# CSR8675_Minimun_System.net
KiCad netlist of a schematic drawn in EasyEDA Pro
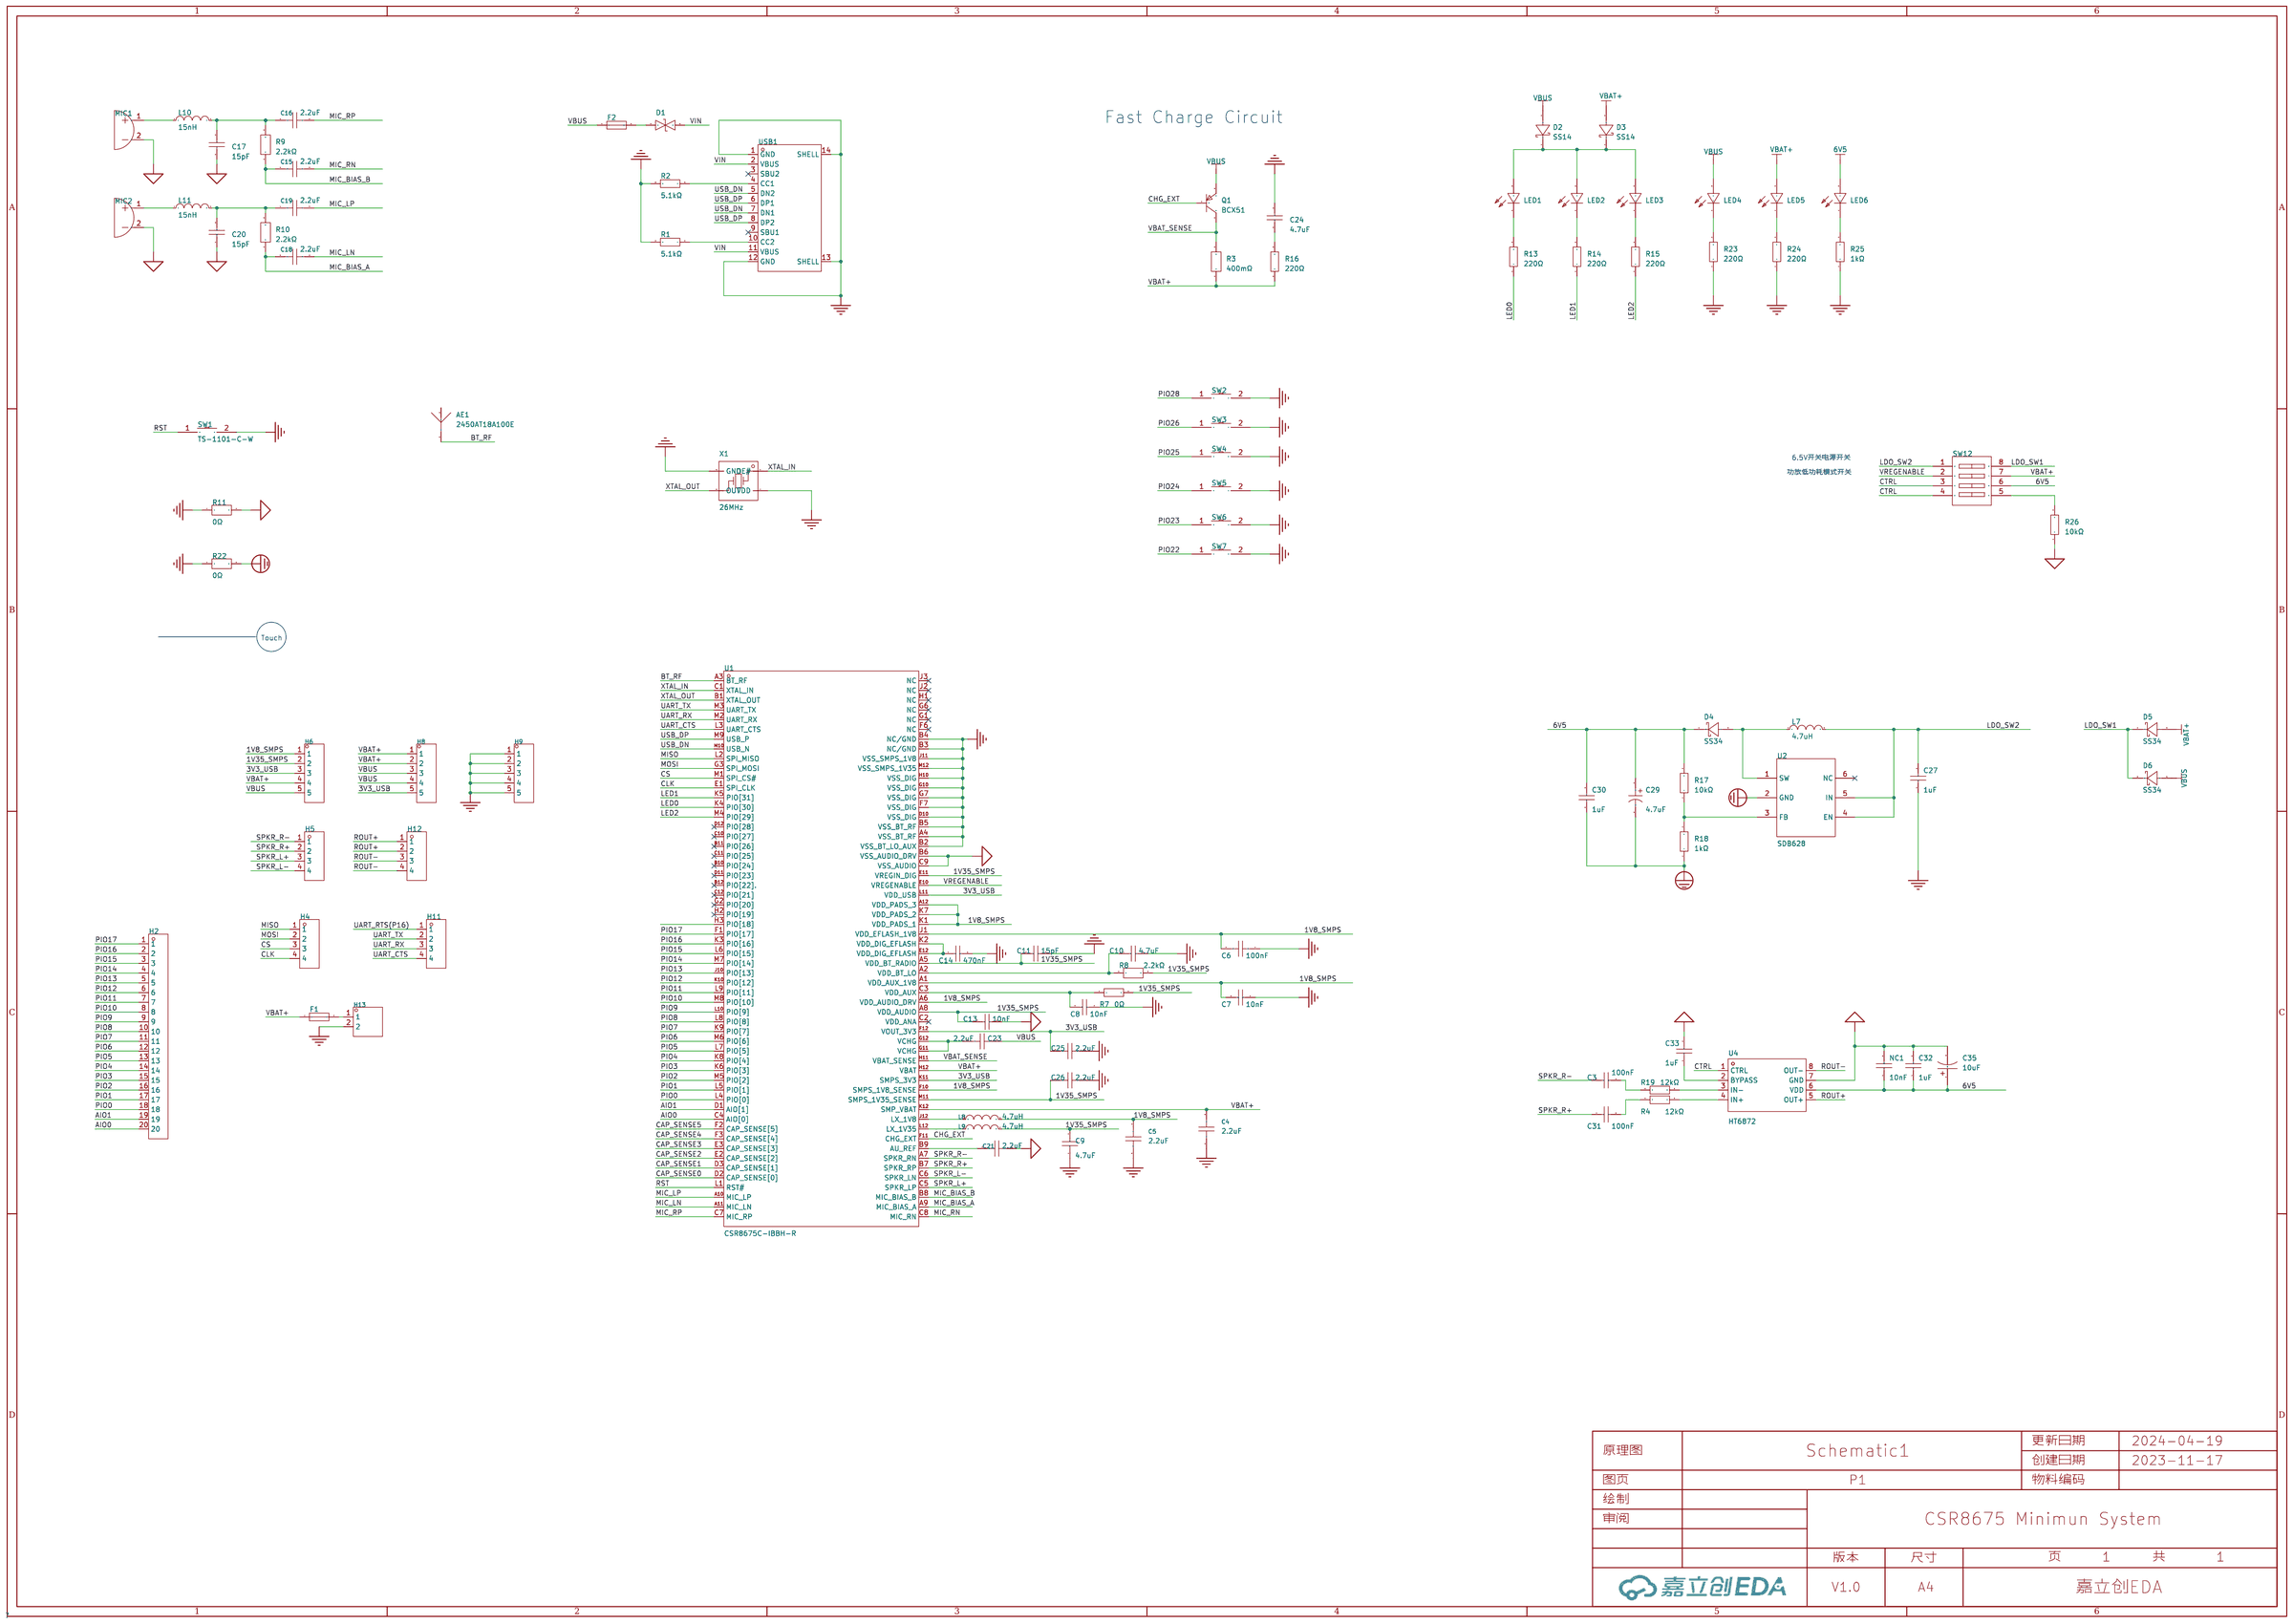
[diagram p0: schematic sheet]

(export (version "E")
  (design (tool "Eeschema 10.0.6"))
  (components
    (comp (ref "AE1")
      (value "2450AT18A100E")
      (footprint "easyedapro:ANT-SMD_L3.2-W1.6")
      (description "天线类型:2.4G天线;中心频点:2.4GHz;带宽:-;峰值增益:0.5dBi;极化方式:-;功率容量:2W;驻波比:-;")
      (fields (field (name "Manufacturer") "JOHANSON(约翰逊)"))
      (libsource (lib "easyedapro") (part "2450AT18A100E"))
    )
    (comp (ref "C3")
      (value "100nF")
      (footprint "easyedapro:C0603")
      (description "容值:100nF;精度:±10%;额定电压:50V;材质(温度系数):X7R;")
      (fields (field (name "Manufacturer Part") "0603B104K500NT") (field (name "Manufacturer") "FH(风华)"))
      (libsource (lib "easyedapro") (part "0603B104K500NT"))
    )
    (comp (ref "C4")
      (value "2.2uF")
      (footprint "easyedapro:C0603")
      (description "容值:2.2uF;精度:±10%;额定电压:50V;材质(温度系数):X5R;")
      (fields
        (field (name "Manufacturer Part") "CL10A225KB8NNNC")
        (field (name "Manufacturer") "SAMSUNG(三星)")
      )
      (libsource (lib "easyedapro") (part "CL10A225KB8NNNC"))
    )
    (comp (ref "C5")
      (value "2.2uF")
      (footprint "easyedapro:C0603")
      (description "容值:2.2uF;精度:±10%;额定电压:50V;材质(温度系数):X5R;")
      (fields
        (field (name "Manufacturer Part") "CL10A225KB8NNNC")
        (field (name "Manufacturer") "SAMSUNG(三星)")
      )
      (libsource (lib "easyedapro") (part "CL10A225KB8NNNC"))
    )
    (comp (ref "C6")
      (value "100nF")
      (footprint "easyedapro:C0603")
      (description "容值:100nF;精度:±10%;额定电压:50V;材质(温度系数):X7R;")
      (fields
        (field (name "Manufacturer Part") "CC0603KRX7R9BB104")
        (field (name "Manufacturer") "YAGEO(国巨)")
      )
      (libsource (lib "easyedapro") (part "CC0603KRX7R9BB104"))
    )
    (comp (ref "C7")
      (value "10nF")
      (footprint "easyedapro:C0603")
      (description "容值:10nF;精度:±10%;额定电压:50V;材质(温度系数):X7R;")
      (fields
        (field (name "Manufacturer Part") "CC0603KRX7R9BB103")
        (field (name "Manufacturer") "YAGEO(国巨)")
      )
      (libsource (lib "easyedapro") (part "CC0603KRX7R9BB103"))
    )
    (comp (ref "C8")
      (value "10nF")
      (footprint "easyedapro:C0603")
      (description "容值:10nF;精度:±10%;额定电压:50V;材质(温度系数):X7R;")
      (fields
        (field (name "Manufacturer Part") "CC0603KRX7R9BB103")
        (field (name "Manufacturer") "YAGEO(国巨)")
      )
      (libsource (lib "easyedapro") (part "CC0603KRX7R9BB103"))
    )
    (comp (ref "C9")
      (value "4.7uF")
      (footprint "easyedapro:C0805")
      (description "容值:4.7uF;精度:±10%;额定电压:25V;材质(温度系数):X5R;")
      (fields
        (field (name "Manufacturer Part") "CL21A475KAQNNNE")
        (field (name "Manufacturer") "SAMSUNG(三星)")
      )
      (libsource (lib "easyedapro") (part "CL21A475KAQNNNE"))
    )
    (comp (ref "C10")
      (value "4.7uF")
      (footprint "easyedapro:C0603")
      (description "容值:4.7uF;精度:±10%;额定电压:16V;材质(温度系数):X5R;")
      (fields
        (field (name "Manufacturer Part") "CL10A475KO8NNNC")
        (field (name "Manufacturer") "SAMSUNG(三星)")
      )
      (libsource (lib "easyedapro") (part "CL10A475KO8NNNC"))
    )
    (comp (ref "C11")
      (value "15pF")
      (footprint "easyedapro:C0603")
      (description "容值:15pF;精度:±5%;额定电压:50V;材质(温度系数):NP0;")
      (fields
        (field (name "Manufacturer Part") "CC0603JRNPO9BN150")
        (field (name "Manufacturer") "YAGEO(国巨)")
      )
      (libsource (lib "easyedapro") (part "CC0603JRNPO9BN150"))
    )
    (comp (ref "C13")
      (value "10nF")
      (footprint "easyedapro:C0603")
      (description "容值:10nF;精度:±10%;额定电压:50V;材质(温度系数):X7R;")
      (fields
        (field (name "Manufacturer Part") "CC0603KRX7R9BB103")
        (field (name "Manufacturer") "YAGEO(国巨)")
      )
      (libsource (lib "easyedapro") (part "CC0603KRX7R9BB103"))
    )
    (comp (ref "C14")
      (value "470nF")
      (footprint "easyedapro:C0603")
      (description "容值:470nF;精度:±10%;额定电压:25V;材质(温度系数):X7R;")
      (fields
        (field (name "Manufacturer Part") "CL10B474KA8NNNC")
        (field (name "Manufacturer") "SAMSUNG(三星)")
      )
      (libsource (lib "easyedapro") (part "CL10B474KA8NNNC"))
    )
    (comp (ref "C15")
      (value "2.2uF")
      (footprint "easyedapro:C0603")
      (description "容值:2.2uF;精度:±10%;额定电压:50V;材质(温度系数):X5R;")
      (fields
        (field (name "Manufacturer Part") "CL10A225KB8NNNC")
        (field (name "Manufacturer") "SAMSUNG(三星)")
      )
      (libsource (lib "easyedapro") (part "CL10A225KB8NNNC"))
    )
    (comp (ref "C16")
      (value "2.2uF")
      (footprint "easyedapro:C0603")
      (description "容值:2.2uF;精度:±10%;额定电压:50V;材质(温度系数):X5R;")
      (fields
        (field (name "Manufacturer Part") "CL10A225KB8NNNC")
        (field (name "Manufacturer") "SAMSUNG(三星)")
      )
      (libsource (lib "easyedapro") (part "CL10A225KB8NNNC"))
    )
    (comp (ref "C17")
      (value "15pF")
      (footprint "easyedapro:C0603")
      (description "容值:15pF;精度:±5%;额定电压:50V;材质(温度系数):NP0;")
      (fields
        (field (name "Manufacturer Part") "CC0603JRNPO9BN150")
        (field (name "Manufacturer") "YAGEO(国巨)")
      )
      (libsource (lib "easyedapro") (part "CC0603JRNPO9BN150"))
    )
    (comp (ref "C18")
      (value "2.2uF")
      (footprint "easyedapro:C0603")
      (description "容值:2.2uF;精度:±10%;额定电压:50V;材质(温度系数):X5R;")
      (fields
        (field (name "Manufacturer Part") "CL10A225KB8NNNC")
        (field (name "Manufacturer") "SAMSUNG(三星)")
      )
      (libsource (lib "easyedapro") (part "CL10A225KB8NNNC"))
    )
    (comp (ref "C19")
      (value "2.2uF")
      (footprint "easyedapro:C0603")
      (description "容值:2.2uF;精度:±10%;额定电压:50V;材质(温度系数):X5R;")
      (fields
        (field (name "Manufacturer Part") "CL10A225KB8NNNC")
        (field (name "Manufacturer") "SAMSUNG(三星)")
      )
      (libsource (lib "easyedapro") (part "CL10A225KB8NNNC"))
    )
    (comp (ref "C20")
      (value "15pF")
      (footprint "easyedapro:C0603")
      (description "容值:15pF;精度:±5%;额定电压:50V;材质(温度系数):NP0;")
      (fields
        (field (name "Manufacturer Part") "CC0603JRNPO9BN150")
        (field (name "Manufacturer") "YAGEO(国巨)")
      )
      (libsource (lib "easyedapro") (part "CC0603JRNPO9BN150"))
    )
    (comp (ref "C21")
      (value "2.2uF")
      (footprint "easyedapro:C0603")
      (description "容值:2.2uF;精度:±10%;额定电压:50V;材质(温度系数):X5R;")
      (fields
        (field (name "Manufacturer Part") "CL10A225KB8NNNC")
        (field (name "Manufacturer") "SAMSUNG(三星)")
      )
      (libsource (lib "easyedapro") (part "CL10A225KB8NNNC"))
    )
    (comp (ref "C23")
      (value "2.2uF")
      (footprint "easyedapro:C0805")
      (description "容值:2.2uF;精度:±10%;额定电压:100V;材质(温度系数):X7T;")
      (fields
        (field (name "Manufacturer Part") "GRM21BD72A225KE01L")
        (field (name "Manufacturer") "muRata(村田)")
      )
      (libsource (lib "easyedapro") (part "GRM21BD72A225KE01L"))
    )
    (comp (ref "C24")
      (value "4.7uF")
      (footprint "easyedapro:C0805")
      (description "容值:4.7uF;精度:±10%;额定电压:25V;材质(温度系数):X5R;")
      (fields
        (field (name "Manufacturer Part") "CL21A475KAQNNNE")
        (field (name "Manufacturer") "SAMSUNG(三星)")
      )
      (libsource (lib "easyedapro") (part "CL21A475KAQNNNE"))
    )
    (comp (ref "C25")
      (value "2.2uF")
      (footprint "easyedapro:C0805")
      (description "容值:2.2uF;精度:±10%;额定电压:100V;材质(温度系数):X7T;")
      (fields
        (field (name "Manufacturer Part") "GRM21BD72A225KE01L")
        (field (name "Manufacturer") "muRata(村田)")
      )
      (libsource (lib "easyedapro") (part "GRM21BD72A225KE01L"))
    )
    (comp (ref "C26")
      (value "2.2uF")
      (footprint "easyedapro:C0805")
      (description "容值:2.2uF;精度:±10%;额定电压:100V;材质(温度系数):X7T;")
      (fields
        (field (name "Manufacturer Part") "GRM21BD72A225KE01L")
        (field (name "Manufacturer") "muRata(村田)")
      )
      (libsource (lib "easyedapro") (part "GRM21BD72A225KE01L"))
    )
    (comp (ref "C27")
      (value "1uF")
      (footprint "easyedapro:C0603")
      (description "容值:1uF;精度:±10%;额定电压:50V;材质(温度系数):X5R;")
      (fields
        (field (name "Manufacturer Part") "CL10A105KB8NNNC")
        (field (name "Manufacturer") "SAMSUNG(三星)")
      )
      (libsource (lib "easyedapro") (part "CL10A105KB8NNNC"))
    )
    (comp (ref "C29")
      (value "4.7uF")
      (footprint "easyedapro:CAP-TH_BD5.0-P2.00-D0.5-FD")
      (description "容值:4.7uF;精度:±20%;额定电压:50V;纹波电流:-;等效串联电阻:-;")
      (fields (field (name "Manufacturer Part") "KM1H4R7M0407") (field (name "Manufacturer") "ROQANG(容强)"))
      (libsource (lib "easyedapro") (part "KM1H4R7M0407"))
    )
    (comp (ref "C30")
      (value "1uF")
      (footprint "easyedapro:C0603")
      (description "容值:1uF;精度:±10%;额定电压:50V;材质(温度系数):X5R;")
      (fields
        (field (name "Manufacturer Part") "CL10A105KB8NNNC")
        (field (name "Manufacturer") "SAMSUNG(三星)")
      )
      (libsource (lib "easyedapro") (part "CL10A105KB8NNNC"))
    )
    (comp (ref "C31")
      (value "100nF")
      (footprint "easyedapro:C0603")
      (description "容值:100nF;精度:±10%;额定电压:50V;材质(温度系数):X7R;")
      (fields (field (name "Manufacturer Part") "0603B104K500NT") (field (name "Manufacturer") "FH(风华)"))
      (libsource (lib "easyedapro") (part "0603B104K500NT"))
    )
    (comp (ref "C32")
      (value "1uF")
      (footprint "easyedapro:C0603")
      (description "容值:1uF;精度:±10%;额定电压:50V;材质(温度系数):X5R;")
      (fields
        (field (name "Manufacturer Part") "CL10A105KB8NNNC")
        (field (name "Manufacturer") "SAMSUNG(三星)")
      )
      (libsource (lib "easyedapro") (part "CL10A105KB8NNNC"))
    )
    (comp (ref "C33")
      (value "1uF")
      (footprint "easyedapro:C0603")
      (description "容值:1uF;精度:±10%;额定电压:50V;材质(温度系数):X5R;")
      (fields
        (field (name "Manufacturer Part") "CL10A105KB8NNNC")
        (field (name "Manufacturer") "SAMSUNG(三星)")
      )
      (libsource (lib "easyedapro") (part "CL10A105KB8NNNC"))
    )
    (comp (ref "C35")
      (value "10uF")
      (footprint "easyedapro:CAP-TH_BD5.0-P2.00-D0.8-FD")
      (description "容值:10uF;精度:±20%;额定电压:50V;纹波电流:50mA@120Hz;等效串联电阻:-;")
      (fields
        (field (name "Manufacturer Part") "01EC1809SHC10UF50V")
        (field (name "Manufacturer") "KNSCHA(科尼盛)")
      )
      (libsource (lib "easyedapro") (part "01EC1809SHC10UF50V"))
    )
    (comp (ref "D1")
      (value "0603ESDA-05N")
      (footprint "easyedapro:D0603-BI")
      (description "极性:双向;反向截止电压(Vrwm):5V;最大钳位电压:50V;")
      (fields (field (name "Manufacturer") "BORN(伯恩半导体)"))
      (libsource (lib "easyedapro") (part "0603ESDA-05N"))
    )
    (comp (ref "D2")
      (value "SS14")
      (footprint "easyedapro:SOD-123FL_L2.8-W1.8-LS3.7-RD")
      (description "二极管配置:-;正向压降(Vf):550mV@1A;直流反向耐压(Vr):40V;平均整流电流(Io):1A;")
      (fields (field (name "Manufacturer") "KUU"))
      (libsource (lib "easyedapro") (part "SS14_C2909920"))
    )
    (comp (ref "D3")
      (value "SS14")
      (footprint "easyedapro:SOD-123FL_L2.8-W1.8-LS3.7-RD")
      (description "二极管配置:-;正向压降(Vf):550mV@1A;直流反向耐压(Vr):40V;平均整流电流(Io):1A;")
      (fields (field (name "Manufacturer") "KUU"))
      (libsource (lib "easyedapro") (part "SS14_C2909920"))
    )
    (comp (ref "D4")
      (value "SS34")
      (footprint "easyedapro:SMA_L4.3-W2.5-LS5.0-RD")
      (description "二极管配置:独立式;正向压降(Vf):550mV@3A;直流反向耐压(Vr):40V;平均整流电流(Io):3A;")
      (fields (field (name "Manufacturer") "TWGMC(台湾迪嘉)"))
      (libsource (lib "easyedapro") (part "SS34_C727060"))
    )
    (comp (ref "D5")
      (value "SS34")
      (footprint "easyedapro:SMA_L4.3-W2.5-LS5.0-RD")
      (description "二极管配置:独立式;正向压降(Vf):550mV@3A;直流反向耐压(Vr):40V;平均整流电流(Io):3A;")
      (fields (field (name "Manufacturer") "TWGMC(台湾迪嘉)"))
      (libsource (lib "easyedapro") (part "SS34_C727060"))
    )
    (comp (ref "D6")
      (value "SS34")
      (footprint "easyedapro:SMA_L4.3-W2.5-LS5.0-RD")
      (description "二极管配置:独立式;正向压降(Vf):550mV@3A;直流反向耐压(Vr):40V;平均整流电流(Io):3A;")
      (fields (field (name "Manufacturer") "TWGMC(台湾迪嘉)"))
      (libsource (lib "easyedapro") (part "SS34_C727060"))
    )
    (comp (ref "F1")
      (value "BSMD1210L-500")
      (footprint "easyedapro:F1210")
      (description "最大电压:6V;最大电流:50A;保持电流:5A;跳闸电流:10A;")
      (fields (field (name "Manufacturer") "BHFUSE(佰宏)"))
      (libsource (lib "easyedapro") (part "BSMD1210L-500"))
    )
    (comp (ref "F2")
      (value "BSMD1210L-500")
      (footprint "easyedapro:F1210")
      (description "最大电压:6V;最大电流:50A;保持电流:5A;跳闸电流:10A;")
      (fields (field (name "Manufacturer") "BHFUSE(佰宏)"))
      (libsource (lib "easyedapro") (part "BSMD1210L-500"))
    )
    (comp (ref "H2")
      (value "~")
      (footprint "easyedapro:HDR-TH_20P-P2.54-V-M-1")
      (libsource (lib "easyedapro") (part "HDR_2.54-1x20P"))
    )
    (comp (ref "H4")
      (value "~")
      (footprint "easyedapro:HDR-TH_4P-P2.54-V-M")
      (libsource (lib "easyedapro") (part "PZ254V-11-04P"))
    )
    (comp (ref "H5")
      (value "~")
      (footprint "easyedapro:HDR-TH_4P-P2.54-V-M")
      (libsource (lib "easyedapro") (part "PZ254V-11-04P"))
    )
    (comp (ref "H6")
      (value "~")
      (footprint "easyedapro:HDR-TH_5P-P2.54-V-M")
      (libsource (lib "easyedapro") (part "MTP125-1105S1"))
    )
    (comp (ref "H8")
      (value "~")
      (footprint "easyedapro:HDR-TH_5P-P2.54-V-M")
      (libsource (lib "easyedapro") (part "MTP125-1105S1"))
    )
    (comp (ref "H9")
      (value "~")
      (footprint "easyedapro:HDR-TH_5P-P2.54-V-M")
      (libsource (lib "easyedapro") (part "MTP125-1105S1"))
    )
    (comp (ref "H11")
      (value "~")
      (footprint "easyedapro:HDR-TH_4P-P2.54-V-M")
      (libsource (lib "easyedapro") (part "PZ254V-11-04P"))
    )
    (comp (ref "H12")
      (value "~")
      (footprint "easyedapro:HDR-TH_4P-P2.54-V-M")
      (libsource (lib "easyedapro") (part "PZ254V-11-04P"))
    )
    (comp (ref "H13")
      (value "~")
      (footprint "easyedapro:HDR-TH_2P-P2.54-V-M-1")
      (libsource (lib "easyedapro") (part "210S-1*2P L=11.6MMGold-plated black"))
    )
    (comp (ref "L7")
      (value "4.7uH")
      (footprint "easyedapro:IND-SMD_L4.4-W4.2")
      (description "电感值:4.7uH;精度:±20%;额定电流:2.8A;饱和电流(Isat):3A;类型:一体成型电感;")
      (fields (field (name "Manufacturer Part") "FXL0420-4R7-M") (field (name "Manufacturer") "cjiang(长江微电)"))
      (libsource (lib "easyedapro") (part "FXL0420-4R7-M"))
    )
    (comp (ref "L8")
      (value "4.7uH")
      (footprint "easyedapro:L0805")
      (description "电感值:4.7uH;精度:±20%;额定电流:800mA;饱和电流(Isat):-;直流电阻(DCR):288mΩ;")
      (fields (field (name "Manufacturer Part") "LQM21PN4R7MGRD") (field (name "Manufacturer") "muRata(村田)"))
      (libsource (lib "easyedapro") (part "LQM21PN4R7MGRD"))
    )
    (comp (ref "L9")
      (value "4.7uH")
      (footprint "easyedapro:L0805")
      (description "电感值:4.7uH;精度:±20%;额定电流:800mA;饱和电流(Isat):-;直流电阻(DCR):288mΩ;")
      (fields (field (name "Manufacturer Part") "LQM21PN4R7MGRD") (field (name "Manufacturer") "muRata(村田)"))
      (libsource (lib "easyedapro") (part "LQM21PN4R7MGRD"))
    )
    (comp (ref "L10")
      (value "15nH")
      (footprint "easyedapro:L0805")
      (description "电感值:15nH;精度:±5%;额定电流:300mA;饱和电流(Isat):-;直流电阻(DCR):400mΩ;")
      (fields (field (name "Manufacturer Part") "VHF201209H15NJT") (field (name "Manufacturer") "FH(风华)"))
      (libsource (lib "easyedapro") (part "VHF201209H15NJT"))
    )
    (comp (ref "L11")
      (value "15nH")
      (footprint "easyedapro:L0805")
      (description "电感值:15nH;精度:±5%;额定电流:300mA;饱和电流(Isat):-;直流电阻(DCR):400mΩ;")
      (fields (field (name "Manufacturer Part") "VHF201209H15NJT") (field (name "Manufacturer") "FH(风华)"))
      (libsource (lib "easyedapro") (part "VHF201209H15NJT"))
    )
    (comp (ref "LED1")
      (value "NCD0603R1")
      (footprint "easyedapro:LED0603-RD_RED")
      (fields (field (name "Manufacturer") "国星光电"))
      (libsource (lib "easyedapro") (part "FC-DA1608HRK-620D"))
    )
    (comp (ref "LED2")
      (value "NCD0603R1")
      (footprint "easyedapro:LED0603-RD_RED")
      (fields (field (name "Manufacturer") "国星光电"))
      (libsource (lib "easyedapro") (part "FC-DA1608HRK-620D"))
    )
    (comp (ref "LED3")
      (value "NCD0603R1")
      (footprint "easyedapro:LED0603-RD_RED")
      (fields (field (name "Manufacturer") "国星光电"))
      (libsource (lib "easyedapro") (part "FC-DA1608HRK-620D"))
    )
    (comp (ref "LED4")
      (value "NCD0603R1")
      (footprint "easyedapro:LED0603-RD_RED")
      (fields (field (name "Manufacturer") "国星光电"))
      (libsource (lib "easyedapro") (part "FC-DA1608HRK-620D"))
    )
    (comp (ref "LED5")
      (value "NCD0603R1")
      (footprint "easyedapro:LED0603-RD_RED")
      (fields (field (name "Manufacturer") "国星光电"))
      (libsource (lib "easyedapro") (part "FC-DA1608HRK-620D"))
    )
    (comp (ref "LED6")
      (value "NCD0603R1")
      (footprint "easyedapro:LED0603-RD_RED")
      (fields (field (name "Manufacturer") "国星光电"))
      (libsource (lib "easyedapro") (part "FC-DA1608HRK-620D"))
    )
    (comp (ref "MIC1")
      (value "GMI6027P-34DB")
      (footprint "easyedapro:MIC-TH_BD6.0-P1.90-D0.4-L")
      (fields (field (name "Manufacturer") "INGHAi(赢海)"))
      (libsource (lib "easyedapro") (part "GMI6027P-34DB"))
    )
    (comp (ref "MIC2")
      (value "GMI6027P-34DB")
      (footprint "easyedapro:MIC-TH_BD6.0-P1.90-D0.4-L")
      (fields (field (name "Manufacturer") "INGHAi(赢海)"))
      (libsource (lib "easyedapro") (part "GMI6027P-34DB"))
    )
    (comp (ref "NC1")
      (value "10nF")
      (footprint "easyedapro:C0603")
      (description "容值:10nF;精度:±10%;额定电压:50V;材质(温度系数):X7R;")
      (fields
        (field (name "Manufacturer Part") "CC0603KRX7R9BB103")
        (field (name "Manufacturer") "YAGEO(国巨)")
      )
      (libsource (lib "easyedapro") (part "CC0603KRX7R9BB103"))
    )
    (comp (ref "Q1")
      (value "BCX51")
      (footprint "easyedapro:SOT-89-3_L4.5-W2.5-P1.50-LS4.2-BR")
      (description "晶体管类型:PNP;集电极电流(Ic):1A;集射极击穿电压(Vceo):45V;功率(Pd):1W;直流电流增益(hFE@Ic,Vce):25@5mA,2V;")
      (fields (field (name "Manufacturer") "SHIKUES(时科)"))
      (libsource (lib "easyedapro") (part "BCX51"))
    )
    (comp (ref "R1")
      (value "5.1kΩ")
      (footprint "easyedapro:R0603")
      (description "电阻类型:厚膜电阻;阻值:5.1kΩ;精度:±1%;功率:100mW;最大工作电压:75V;温度系数:±100ppm/°C;")
      (fields
        (field (name "Manufacturer Part") "0603WAF5101T5E")
        (field (name "Manufacturer") "UNI-ROYAL(厚声)")
      )
      (libsource (lib "easyedapro") (part "0603WAF5101T5E"))
    )
    (comp (ref "R2")
      (value "5.1kΩ")
      (footprint "easyedapro:R0603")
      (description "电阻类型:厚膜电阻;阻值:5.1kΩ;精度:±1%;功率:100mW;最大工作电压:75V;温度系数:±100ppm/°C;")
      (fields
        (field (name "Manufacturer Part") "0603WAF5101T5E")
        (field (name "Manufacturer") "UNI-ROYAL(厚声)")
      )
      (libsource (lib "easyedapro") (part "0603WAF5101T5E"))
    )
    (comp (ref "R3")
      (value "400mΩ")
      (footprint "easyedapro:R0805")
      (description "电阻类型:厚膜电阻;阻值:400mΩ;精度:±1%;功率:125mW;最大工作电压:300V;温度系数:±300ppm/°C;")
      (fields (field (name "Manufacturer Part") "FRL0805FR400TS") (field (name "Manufacturer") "FOJAN(富捷)"))
      (libsource (lib "easyedapro") (part "FRL0805FR400TS"))
    )
    (comp (ref "R4")
      (value "12kΩ")
      (footprint "easyedapro:R0603")
      (description "电阻类型:厚膜电阻;阻值:12kΩ;精度:±1%;功率:100mW;最大工作电压:75V;温度系数:±100ppm/°C;")
      (fields
        (field (name "Manufacturer Part") "0603WAF1202T5E")
        (field (name "Manufacturer") "UNI-ROYAL(厚声)")
      )
      (libsource (lib "easyedapro") (part "0603WAF1202T5E"))
    )
    (comp (ref "R7")
      (value "0Ω")
      (footprint "easyedapro:R0603")
      (description "电阻类型:厚膜电阻;阻值:0Ω;精度:±1%;功率:100mW;最大工作电压:75V;")
      (fields
        (field (name "Manufacturer Part") "0603WAF0000T5E")
        (field (name "Manufacturer") "UNI-ROYAL(厚声)")
      )
      (libsource (lib "easyedapro") (part "0603WAF0000T5E"))
    )
    (comp (ref "R8")
      (value "2.2kΩ")
      (footprint "easyedapro:R0603")
      (description "电阻类型:厚膜电阻;阻值:2.2kΩ;精度:±5%;功率:100mW;最大工作电压:75V;温度系数:±100ppm/°C;")
      (fields (field (name "Manufacturer Part") "FRC0603J222 TS") (field (name "Manufacturer") "FOJAN(富捷)"))
      (libsource (lib "easyedapro") (part "FRC0603J222 TS"))
    )
    (comp (ref "R9")
      (value "2.2kΩ")
      (footprint "easyedapro:R0603")
      (description "电阻类型:厚膜电阻;阻值:2.2kΩ;精度:±5%;功率:100mW;最大工作电压:75V;温度系数:±100ppm/°C;")
      (fields (field (name "Manufacturer Part") "FRC0603J222 TS") (field (name "Manufacturer") "FOJAN(富捷)"))
      (libsource (lib "easyedapro") (part "FRC0603J222 TS"))
    )
    (comp (ref "R10")
      (value "2.2kΩ")
      (footprint "easyedapro:R0603")
      (description "电阻类型:厚膜电阻;阻值:2.2kΩ;精度:±5%;功率:100mW;最大工作电压:75V;温度系数:±100ppm/°C;")
      (fields (field (name "Manufacturer Part") "FRC0603J222 TS") (field (name "Manufacturer") "FOJAN(富捷)"))
      (libsource (lib "easyedapro") (part "FRC0603J222 TS"))
    )
    (comp (ref "R11")
      (value "0Ω")
      (footprint "easyedapro:R0805")
      (description "电阻类型:厚膜电阻;阻值:0Ω;精度:±5%;功率:125mW;最大工作电压:150V;")
      (fields (field (name "Manufacturer Part") "FRC0805P000 TS") (field (name "Manufacturer") "FOJAN(富捷)"))
      (libsource (lib "easyedapro") (part "FRC0805P000 TS"))
    )
    (comp (ref "R13")
      (value "220Ω")
      (footprint "easyedapro:R0603")
      (description "电阻类型:厚膜电阻;阻值:220Ω;精度:±5%;功率:100mW;最大工作电压:75V;温度系数:±100ppm/°C;")
      (fields
        (field (name "Manufacturer Part") "0603WAJ0221T5E")
        (field (name "Manufacturer") "UNI-ROYAL(厚声)")
      )
      (libsource (lib "easyedapro") (part "0603WAJ0221T5E"))
    )
    (comp (ref "R14")
      (value "220Ω")
      (footprint "easyedapro:R0603")
      (description "电阻类型:厚膜电阻;阻值:220Ω;精度:±5%;功率:100mW;最大工作电压:75V;温度系数:±100ppm/°C;")
      (fields
        (field (name "Manufacturer Part") "0603WAJ0221T5E")
        (field (name "Manufacturer") "UNI-ROYAL(厚声)")
      )
      (libsource (lib "easyedapro") (part "0603WAJ0221T5E"))
    )
    (comp (ref "R15")
      (value "220Ω")
      (footprint "easyedapro:R0603")
      (description "电阻类型:厚膜电阻;阻值:220Ω;精度:±5%;功率:100mW;最大工作电压:75V;温度系数:±100ppm/°C;")
      (fields
        (field (name "Manufacturer Part") "0603WAJ0221T5E")
        (field (name "Manufacturer") "UNI-ROYAL(厚声)")
      )
      (libsource (lib "easyedapro") (part "0603WAJ0221T5E"))
    )
    (comp (ref "R16")
      (value "220Ω")
      (footprint "easyedapro:R0805")
      (description "电阻类型:厚膜电阻;阻值:220Ω;精度:±1%;功率:125mW;最大工作电压:150V;温度系数:±100ppm/°C;")
      (fields
        (field (name "Manufacturer Part") "0805W8F2200T5E")
        (field (name "Manufacturer") "UNI-ROYAL(厚声)")
      )
      (libsource (lib "easyedapro") (part "0805W8F2200T5E"))
    )
    (comp (ref "R17")
      (value "10kΩ")
      (footprint "easyedapro:R0603")
      (description "电阻类型:厚膜电阻;阻值:10kΩ;精度:±1%;功率:100mW;最大工作电压:75V;温度系数:±100ppm/°C;")
      (fields
        (field (name "Manufacturer Part") "0603WAF1002T5E")
        (field (name "Manufacturer") "UNI-ROYAL(厚声)")
      )
      (libsource (lib "easyedapro") (part "0603WAF1002T5E"))
    )
    (comp (ref "R18")
      (value "1kΩ")
      (footprint "easyedapro:R0603")
      (description "电阻类型:厚膜电阻;阻值:1kΩ;精度:±1%;功率:100mW;最大工作电压:75V;温度系数:±100ppm/°C;")
      (fields (field (name "Manufacturer Part") "RC0603FR-071KL") (field (name "Manufacturer") "YAGEO(国巨)"))
      (libsource (lib "easyedapro") (part "RC0603FR-071KL"))
    )
    (comp (ref "R19")
      (value "12kΩ")
      (footprint "easyedapro:R0603")
      (description "电阻类型:厚膜电阻;阻值:12kΩ;精度:±1%;功率:100mW;最大工作电压:75V;温度系数:±100ppm/°C;")
      (fields
        (field (name "Manufacturer Part") "0603WAF1202T5E")
        (field (name "Manufacturer") "UNI-ROYAL(厚声)")
      )
      (libsource (lib "easyedapro") (part "0603WAF1202T5E"))
    )
    (comp (ref "R22")
      (value "0Ω")
      (footprint "easyedapro:R0805")
      (description "电阻类型:厚膜电阻;阻值:0Ω;精度:±5%;功率:125mW;最大工作电压:150V;")
      (fields (field (name "Manufacturer Part") "FRC0805P000 TS") (field (name "Manufacturer") "FOJAN(富捷)"))
      (libsource (lib "easyedapro") (part "FRC0805P000 TS"))
    )
    (comp (ref "R23")
      (value "220Ω")
      (footprint "easyedapro:R0603")
      (description "电阻类型:厚膜电阻;阻值:220Ω;精度:±5%;功率:100mW;最大工作电压:75V;温度系数:±100ppm/°C;")
      (fields
        (field (name "Manufacturer Part") "0603WAJ0221T5E")
        (field (name "Manufacturer") "UNI-ROYAL(厚声)")
      )
      (libsource (lib "easyedapro") (part "0603WAJ0221T5E"))
    )
    (comp (ref "R24")
      (value "220Ω")
      (footprint "easyedapro:R0603")
      (description "电阻类型:厚膜电阻;阻值:220Ω;精度:±5%;功率:100mW;最大工作电压:75V;温度系数:±100ppm/°C;")
      (fields
        (field (name "Manufacturer Part") "0603WAJ0221T5E")
        (field (name "Manufacturer") "UNI-ROYAL(厚声)")
      )
      (libsource (lib "easyedapro") (part "0603WAJ0221T5E"))
    )
    (comp (ref "R25")
      (value "1kΩ")
      (footprint "easyedapro:R0603")
      (description "电阻类型:厚膜电阻;阻值:1kΩ;精度:±1%;功率:100mW;最大工作电压:75V;温度系数:±100ppm/°C;")
      (fields (field (name "Manufacturer Part") "RC0603FR-071KL") (field (name "Manufacturer") "YAGEO(国巨)"))
      (libsource (lib "easyedapro") (part "RC0603FR-071KL"))
    )
    (comp (ref "R26")
      (value "10kΩ")
      (footprint "easyedapro:R0603")
      (description "电阻类型:厚膜电阻;阻值:10kΩ;精度:±1%;功率:100mW;最大工作电压:75V;温度系数:±100ppm/°C;")
      (fields
        (field (name "Manufacturer Part") "0603WAF1002T5E")
        (field (name "Manufacturer") "UNI-ROYAL(厚声)")
      )
      (libsource (lib "easyedapro") (part "0603WAF1002T5E"))
    )
    (comp (ref "SW1")
      (value "TS-1101-C-W")
      (footprint "easyedapro:SW-SMD_L6.0-W3.3-LS8.0")
      (fields (field (name "Manufacturer") "XKB Connectivity(中国星坤)"))
      (libsource (lib "easyedapro") (part "TS-1101-C-W"))
    )
    (comp (ref "SW2")
      (value "TS-1101-C-W")
      (footprint "easyedapro:SW-SMD_L6.0-W3.3-LS8.0")
      (fields (field (name "Manufacturer") "XKB Connectivity(中国星坤)"))
      (libsource (lib "easyedapro") (part "TS-1101-C-W"))
    )
    (comp (ref "SW3")
      (value "TS-1101-C-W")
      (footprint "easyedapro:SW-SMD_L6.0-W3.3-LS8.0")
      (fields (field (name "Manufacturer") "XKB Connectivity(中国星坤)"))
      (libsource (lib "easyedapro") (part "TS-1101-C-W"))
    )
    (comp (ref "SW4")
      (value "TS-1101-C-W")
      (footprint "easyedapro:SW-SMD_L6.0-W3.3-LS8.0")
      (fields (field (name "Manufacturer") "XKB Connectivity(中国星坤)"))
      (libsource (lib "easyedapro") (part "TS-1101-C-W"))
    )
    (comp (ref "SW5")
      (value "TS-1101-C-W")
      (footprint "easyedapro:SW-SMD_L6.0-W3.3-LS8.0")
      (fields (field (name "Manufacturer") "XKB Connectivity(中国星坤)"))
      (libsource (lib "easyedapro") (part "TS-1101-C-W"))
    )
    (comp (ref "SW6")
      (value "TS-1101-C-W")
      (footprint "easyedapro:SW-SMD_L6.0-W3.3-LS8.0")
      (fields (field (name "Manufacturer") "XKB Connectivity(中国星坤)"))
      (libsource (lib "easyedapro") (part "TS-1101-C-W"))
    )
    (comp (ref "SW7")
      (value "TS-1101-C-W")
      (footprint "easyedapro:SW-SMD_L6.0-W3.3-LS8.0")
      (fields (field (name "Manufacturer") "XKB Connectivity(中国星坤)"))
      (libsource (lib "easyedapro") (part "TS-1101-C-W"))
    )
    (comp (ref "SW12")
      (value "SMXS-04K-TP")
      (footprint "easyedapro:SW-SMD_SMXS-04K-TP")
      (description "类型:-;电路结构:-;开关位数:4位;额定电流:-;额定电压:-;使用寿命:3千次;颜色:黑色;")
      (fields (field (name "Manufacturer") "SM Switch"))
      (libsource (lib "easyedapro") (part "SMXS-04K-TP"))
    )
    (comp (ref "U1")
      (value "CSR8675C-IBBH-R")
      (footprint "easyedapro:BGA-112_L6.5-W6.5-P0.50-TL")
      (description "频率范围:2.4GHz;接口:I2S;应用领域:蓝牙;灵敏度:-90dBm;")
      (fields (field (name "Manufacturer") "Qualcomm"))
      (libsource (lib "easyedapro") (part "CSR8675C-IBBH-R"))
    )
    (comp (ref "U2")
      (value "SDB628")
      (footprint "easyedapro:SOT-23-6_L2.9-W1.6-P0.95-LS2.8-BR")
      (description "功能类型:升压型;输入电压:2V~24V;输出电压:28V;输出电流(最大值):2A;")
      (fields (field (name "Manufacturer") "SHOUDING(首鼎半导体)"))
      (libsource (lib "easyedapro") (part "SDB628"))
    )
    (comp (ref "U4")
      (value "HT6872")
      (footprint "easyedapro:SOP-8_L4.9-W3.9-P1.27-LS6.0-BL")
      (description "功放类型:D类功放;扬声器通道数:单声道;输出功率:3.85Wx1@4Ω;")
      (fields (field (name "Manufacturer") "嘉兴禾润"))
      (libsource (lib "easyedapro") (part "HT6872"))
    )
    (comp (ref "USB1")
      (value "TYPE-C 16PIN 2MD(073)")
      (footprint "easyedapro:USB-C-SMD_TYPE-C-6PIN-2MD-073")
      (description "连接器类型:Type-C;标准:-;公母:母;端口数量:1;触点数量:16P;安装方式:卧贴;额定电流 - 电源:5A;工作温度范围:-25°C~+85°C;")
      (fields (field (name "Manufacturer") "SHOU HAN(首韩)"))
      (libsource (lib "easyedapro") (part "TYPE-C 16PIN 2MD(073)"))
    )
    (comp (ref "X1")
      (value "26MHz")
      (footprint "easyedapro:OSC-SMD_4P-L2.0-W1.6-BL_X201624MKB4SI")
      (description "频率:26MHz;工作电压:1.8V~3.3V;供电电流:4mA;频率稳定度(全温):±10ppm;")
      (fields (field (name "Manufacturer Part") "OT201626MJBA4SL") (field (name "Manufacturer") "YXC(扬兴晶振)"))
      (libsource (lib "easyedapro") (part "OT201626MJBA4SL"))
    )
  )
  (nets
    (net (code "1") (name "/1V8_SMPS") (class "Default")
      (node (ref "C5") (pin "1") (pinfunction "1_1") (pintype "input"))
      (node (ref "C6") (pin "2") (pinfunction "2_2") (pintype "unspecified"))
      (node (ref "C7") (pin "2") (pinfunction "2_2") (pintype "input"))
      (node (ref "H6") (pin "1") (pinfunction "1_1") (pintype "input"))
      (node (ref "L8") (pin "2") (pinfunction "2_2") (pintype "input"))
      (node (ref "U1") (pin "A1") (pinfunction "VDD_AUX_1V8_A1") (pintype "input"))
      (node (ref "U1") (pin "A12") (pinfunction "VDD_PADS_3_A12") (pintype "input"))
      (node (ref "U1") (pin "A6") (pinfunction "VDD_AUDIO_DRV_A6") (pintype "input"))
      (node (ref "U1") (pin "F10") (pinfunction "SMPS_1V8_SENSE_F10") (pintype "input"))
      (node (ref "U1") (pin "J1") (pinfunction "VDD_EFLASH_1V8_J1") (pintype "input"))
      (node (ref "U1") (pin "K1") (pinfunction "VDD_PADS_1_K1") (pintype "input"))
      (node (ref "U1") (pin "K7") (pinfunction "VDD_PADS_2_K7") (pintype "input"))
    )
    (net (code "2") (name "/1V35_SMPS") (class "Default")
      (node (ref "C11") (pin "1") (pinfunction "1_1") (pintype "input"))
      (node (ref "C13") (pin "1") (pinfunction "1_1") (pintype "input"))
      (node (ref "C26") (pin "1") (pinfunction "1_1") (pintype "unspecified"))
      (node (ref "C9") (pin "2") (pinfunction "2_2") (pintype "input"))
      (node (ref "H6") (pin "2") (pinfunction "2_2") (pintype "input"))
      (node (ref "L9") (pin "2") (pinfunction "2_2") (pintype "input"))
      (node (ref "R7") (pin "2") (pinfunction "2_2") (pintype "input"))
      (node (ref "R8") (pin "2") (pinfunction "2_2") (pintype "unspecified"))
      (node (ref "U1") (pin "A5") (pinfunction "VDD_BT_RADIO_A5") (pintype "input"))
      (node (ref "U1") (pin "A8") (pinfunction "VDD_AUDIO_A8") (pintype "input"))
      (node (ref "U1") (pin "E11") (pinfunction "VREGIN_DIG_E11") (pintype "input"))
      (node (ref "U1") (pin "M11") (pinfunction "SMPS_1V35_SENSE_M11") (pintype "input"))
    )
    (net (code "3") (name "/3V3_USB") (class "Default")
      (node (ref "C25") (pin "1") (pinfunction "1_1") (pintype "unspecified"))
      (node (ref "H6") (pin "3") (pinfunction "3_3") (pintype "input"))
      (node (ref "H8") (pin "5") (pinfunction "5_5") (pintype "input"))
      (node (ref "U1") (pin "F12") (pinfunction "VOUT_3V3_F12") (pintype "input"))
      (node (ref "U1") (pin "K11") (pinfunction "SMPS_3V3_K11") (pintype "input"))
      (node (ref "U1") (pin "L11") (pinfunction "VDD_USB_L11") (pintype "input"))
    )
    (net (code "4") (name "/AIO0") (class "Default")
      (node (ref "H2") (pin "20") (pinfunction "20_20") (pintype "input"))
      (node (ref "U1") (pin "C4") (pinfunction "AIO[0]_C4") (pintype "input"))
    )
    (net (code "5") (name "/AIO1") (class "Default")
      (node (ref "H2") (pin "19") (pinfunction "19_19") (pintype "input"))
      (node (ref "U1") (pin "D1") (pinfunction "AIO[1]_D1") (pintype "input"))
    )
    (net (code "6") (name "/BT_RF") (class "Default")
      (node (ref "AE1") (pin "1") (pinfunction "ANT_1") (pintype "input"))
      (node (ref "U1") (pin "A3") (pinfunction "BT_RF_A3") (pintype "input"))
    )
    (net (code "7") (name "/CAP_SENSE0") (class "Default")
      (node (ref "U1") (pin "D2") (pinfunction "CAP_SENSE[0]_D2") (pintype "input"))
    )
    (net (code "8") (name "/CAP_SENSE1") (class "Default")
      (node (ref "U1") (pin "D3") (pinfunction "CAP_SENSE[1]_D3") (pintype "input"))
    )
    (net (code "9") (name "/CAP_SENSE2") (class "Default")
      (node (ref "U1") (pin "E2") (pinfunction "CAP_SENSE[2]_E2") (pintype "input"))
    )
    (net (code "10") (name "/CAP_SENSE3") (class "Default")
      (node (ref "U1") (pin "E3") (pinfunction "CAP_SENSE[3]_E3") (pintype "input"))
    )
    (net (code "11") (name "/CAP_SENSE4") (class "Default")
      (node (ref "U1") (pin "F3") (pinfunction "CAP_SENSE[4]_F3") (pintype "input"))
    )
    (net (code "12") (name "/CAP_SENSE5") (class "Default")
      (node (ref "U1") (pin "F2") (pinfunction "CAP_SENSE[5]_F2") (pintype "input"))
    )
    (net (code "13") (name "/CHG_EXT") (class "Default")
      (node (ref "Q1") (pin "1") (pinfunction "B_1") (pintype "unspecified"))
      (node (ref "U1") (pin "F11") (pinfunction "CHG_EXT_F11") (pintype "input"))
    )
    (net (code "14") (name "/CLK") (class "Default")
      (node (ref "H4") (pin "4") (pinfunction "4_4") (pintype "unspecified"))
      (node (ref "U1") (pin "E1") (pinfunction "SPI_CLK_E1") (pintype "input"))
    )
    (net (code "15") (name "/CS") (class "Default")
      (node (ref "H4") (pin "3") (pinfunction "3_3") (pintype "unspecified"))
      (node (ref "U1") (pin "M1") (pinfunction "SPI_CS#_M1") (pintype "input"))
    )
    (net (code "16") (name "/CTRL") (class "Default")
      (node (ref "SW12") (pin "3") (pinfunction "3_3") (pintype "input"))
      (node (ref "SW12") (pin "4") (pinfunction "4_4") (pintype "input"))
      (node (ref "U4") (pin "1") (pinfunction "CTRL_1") (pintype "unspecified"))
    )
    (net (code "17") (name "/LDO_SW1") (class "Default")
      (node (ref "D5") (pin "1") (pinfunction "C_1") (pintype "unspecified"))
      (node (ref "D6") (pin "1") (pinfunction "C_1") (pintype "unspecified"))
      (node (ref "SW12") (pin "8") (pinfunction "8_8") (pintype "input"))
    )
    (net (code "18") (name "/LDO_SW2") (class "Default")
      (node (ref "C27") (pin "2") (pinfunction "2_2") (pintype "input"))
      (node (ref "L7") (pin "2") (pinfunction "2_2") (pintype "unspecified"))
      (node (ref "SW12") (pin "1") (pinfunction "1_1") (pintype "input"))
      (node (ref "U2") (pin "4") (pinfunction "EN_4") (pintype "input"))
      (node (ref "U2") (pin "5") (pinfunction "IN_5") (pintype "input"))
    )
    (net (code "19") (name "/LED0") (class "Default")
      (node (ref "R13") (pin "1") (pinfunction "1_1") (pintype "input"))
      (node (ref "U1") (pin "K4") (pinfunction "PIO[30]_K4") (pintype "input"))
    )
    (net (code "20") (name "/LED1") (class "Default")
      (node (ref "R14") (pin "1") (pinfunction "1_1") (pintype "input"))
      (node (ref "U1") (pin "K5") (pinfunction "PIO[31]_K5") (pintype "input"))
    )
    (net (code "21") (name "/LED2") (class "Default")
      (node (ref "R15") (pin "1") (pinfunction "1_1") (pintype "input"))
      (node (ref "U1") (pin "M4") (pinfunction "PIO[29]_M4") (pintype "input"))
    )
    (net (code "22") (name "/MIC_BIAS_A") (class "Default")
      (node (ref "C18") (pin "1") (pinfunction "1_1") (pintype "input"))
      (node (ref "R10") (pin "1") (pinfunction "1_1") (pintype "unspecified"))
      (node (ref "U1") (pin "A9") (pinfunction "MIC_BIAS_A_A9") (pintype "input"))
    )
    (net (code "23") (name "/MIC_BIAS_B") (class "Default")
      (node (ref "C15") (pin "1") (pinfunction "1_1") (pintype "input"))
      (node (ref "R9") (pin "1") (pinfunction "1_1") (pintype "unspecified"))
      (node (ref "U1") (pin "B8") (pinfunction "MIC_BIAS_B_B8") (pintype "input"))
    )
    (net (code "24") (name "/MIC_LN") (class "Default")
      (node (ref "C18") (pin "2") (pinfunction "2_2") (pintype "input"))
      (node (ref "U1") (pin "A11") (pinfunction "MIC_LN_A11") (pintype "input"))
    )
    (net (code "25") (name "/MIC_LP") (class "Default")
      (node (ref "C19") (pin "2") (pinfunction "2_2") (pintype "input"))
      (node (ref "U1") (pin "A10") (pinfunction "MIC_LP_A10") (pintype "input"))
    )
    (net (code "26") (name "/MIC_RN") (class "Default")
      (node (ref "C15") (pin "2") (pinfunction "2_2") (pintype "input"))
      (node (ref "U1") (pin "C8") (pinfunction "MIC_RN_C8") (pintype "input"))
    )
    (net (code "27") (name "/MIC_RP") (class "Default")
      (node (ref "C16") (pin "2") (pinfunction "2_2") (pintype "input"))
      (node (ref "U1") (pin "C7") (pinfunction "MIC_RP_C7") (pintype "input"))
    )
    (net (code "28") (name "/MISO") (class "Default")
      (node (ref "H4") (pin "1") (pinfunction "1_1") (pintype "unspecified"))
      (node (ref "U1") (pin "L2") (pinfunction "SPI_MISO_L2") (pintype "input"))
    )
    (net (code "29") (name "/MOSI") (class "Default")
      (node (ref "H4") (pin "2") (pinfunction "2_2") (pintype "unspecified"))
      (node (ref "U1") (pin "G3") (pinfunction "SPI_MOSI_G3") (pintype "input"))
    )
    (net (code "30") (name "/PIO0") (class "Default")
      (node (ref "H2") (pin "18") (pinfunction "18_18") (pintype "input"))
      (node (ref "U1") (pin "L4") (pinfunction "PIO[0]_L4") (pintype "input"))
    )
    (net (code "31") (name "/PIO1") (class "Default")
      (node (ref "H2") (pin "17") (pinfunction "17_17") (pintype "input"))
      (node (ref "U1") (pin "L5") (pinfunction "PIO[1]_L5") (pintype "input"))
    )
    (net (code "32") (name "/PIO2") (class "Default")
      (node (ref "H2") (pin "16") (pinfunction "16_16") (pintype "input"))
      (node (ref "U1") (pin "M5") (pinfunction "PIO[2]_M5") (pintype "input"))
    )
    (net (code "33") (name "/PIO3") (class "Default")
      (node (ref "H2") (pin "15") (pinfunction "15_15") (pintype "input"))
      (node (ref "U1") (pin "K6") (pinfunction "PIO[3]_K6") (pintype "input"))
    )
    (net (code "34") (name "/PIO4") (class "Default")
      (node (ref "H2") (pin "14") (pinfunction "14_14") (pintype "input"))
      (node (ref "U1") (pin "K8") (pinfunction "PIO[4]_K8") (pintype "input"))
    )
    (net (code "35") (name "/PIO5") (class "Default")
      (node (ref "H2") (pin "13") (pinfunction "13_13") (pintype "input"))
      (node (ref "U1") (pin "L7") (pinfunction "PIO[5]_L7") (pintype "input"))
    )
    (net (code "36") (name "/PIO6") (class "Default")
      (node (ref "H2") (pin "12") (pinfunction "12_12") (pintype "input"))
      (node (ref "U1") (pin "M6") (pinfunction "PIO[6]_M6") (pintype "input"))
    )
    (net (code "37") (name "/PIO7") (class "Default")
      (node (ref "H2") (pin "11") (pinfunction "11_11") (pintype "input"))
      (node (ref "U1") (pin "K9") (pinfunction "PIO[7]_K9") (pintype "input"))
    )
    (net (code "38") (name "/PIO8") (class "Default")
      (node (ref "H2") (pin "10") (pinfunction "10_10") (pintype "input"))
      (node (ref "U1") (pin "L8") (pinfunction "PIO[8]_L8") (pintype "input"))
    )
    (net (code "39") (name "/PIO9") (class "Default")
      (node (ref "H2") (pin "9") (pinfunction "9_9") (pintype "input"))
      (node (ref "U1") (pin "L10") (pinfunction "PIO[9]_L10") (pintype "input"))
    )
    (net (code "40") (name "/PIO10") (class "Default")
      (node (ref "H2") (pin "8") (pinfunction "8_8") (pintype "input"))
      (node (ref "U1") (pin "M8") (pinfunction "PIO[10]_M8") (pintype "input"))
    )
    (net (code "41") (name "/PIO11") (class "Default")
      (node (ref "H2") (pin "7") (pinfunction "7_7") (pintype "input"))
      (node (ref "U1") (pin "L9") (pinfunction "PIO[11]_L9") (pintype "input"))
    )
    (net (code "42") (name "/PIO12") (class "Default")
      (node (ref "H2") (pin "6") (pinfunction "6_6") (pintype "input"))
      (node (ref "U1") (pin "K10") (pinfunction "PIO[12]_K10") (pintype "input"))
    )
    (net (code "43") (name "/PIO13") (class "Default")
      (node (ref "H2") (pin "5") (pinfunction "5_5") (pintype "input"))
      (node (ref "U1") (pin "J10") (pinfunction "PIO[13]_J10") (pintype "input"))
    )
    (net (code "44") (name "/PIO14") (class "Default")
      (node (ref "H2") (pin "4") (pinfunction "4_4") (pintype "input"))
      (node (ref "U1") (pin "M7") (pinfunction "PIO[14]_M7") (pintype "input"))
    )
    (net (code "45") (name "/PIO15") (class "Default")
      (node (ref "H2") (pin "3") (pinfunction "3_3") (pintype "input"))
      (node (ref "U1") (pin "L6") (pinfunction "PIO[15]_L6") (pintype "input"))
    )
    (net (code "46") (name "/PIO16") (class "Default")
      (node (ref "H2") (pin "2") (pinfunction "2_2") (pintype "input"))
      (node (ref "U1") (pin "K3") (pinfunction "PIO[16]_K3") (pintype "input"))
    )
    (net (code "47") (name "/PIO17") (class "Default")
      (node (ref "H2") (pin "1") (pinfunction "1_1") (pintype "input"))
      (node (ref "U1") (pin "F1") (pinfunction "PIO[17]_F1") (pintype "input"))
    )
    (net (code "48") (name "/PIO22") (class "Default")
      (node (ref "SW7") (pin "1") (pinfunction "1_1") (pintype "unspecified"))
    )
    (net (code "49") (name "/PIO23") (class "Default")
      (node (ref "SW6") (pin "1") (pinfunction "1_1") (pintype "unspecified"))
    )
    (net (code "50") (name "/PIO24") (class "Default")
      (node (ref "SW5") (pin "1") (pinfunction "1_1") (pintype "unspecified"))
    )
    (net (code "51") (name "/PIO25") (class "Default")
      (node (ref "SW4") (pin "1") (pinfunction "1_1") (pintype "unspecified"))
    )
    (net (code "52") (name "/PIO26") (class "Default")
      (node (ref "SW3") (pin "1") (pinfunction "1_1") (pintype "unspecified"))
    )
    (net (code "53") (name "/PIO28") (class "Default")
      (node (ref "SW2") (pin "1") (pinfunction "1_1") (pintype "unspecified"))
    )
    (net (code "54") (name "/ROUT+") (class "Default")
      (node (ref "H12") (pin "1") (pinfunction "1_1") (pintype "unspecified"))
      (node (ref "H12") (pin "2") (pinfunction "2_2") (pintype "unspecified"))
      (node (ref "U4") (pin "5") (pinfunction "OUT+_5") (pintype "unspecified"))
    )
    (net (code "55") (name "/ROUT-") (class "Default")
      (node (ref "H12") (pin "3") (pinfunction "3_3") (pintype "unspecified"))
      (node (ref "H12") (pin "4") (pinfunction "4_4") (pintype "unspecified"))
      (node (ref "U4") (pin "8") (pinfunction "OUT-_8") (pintype "unspecified"))
    )
    (net (code "56") (name "/RST") (class "Default")
      (node (ref "SW1") (pin "1") (pinfunction "1_1") (pintype "unspecified"))
      (node (ref "U1") (pin "L1") (pinfunction "RST#_L1") (pintype "input"))
    )
    (net (code "57") (name "/SPKR_L+") (class "Default")
      (node (ref "H5") (pin "3") (pinfunction "3_3") (pintype "unspecified"))
      (node (ref "U1") (pin "C5") (pinfunction "SPKR_LP_C5") (pintype "input"))
    )
    (net (code "58") (name "/SPKR_L-") (class "Default")
      (node (ref "H5") (pin "4") (pinfunction "4_4") (pintype "unspecified"))
      (node (ref "U1") (pin "C6") (pinfunction "SPKR_LN_C6") (pintype "input"))
    )
    (net (code "59") (name "/SPKR_R+") (class "Default")
      (node (ref "C31") (pin "1") (pinfunction "1_1") (pintype "input"))
      (node (ref "H5") (pin "2") (pinfunction "2_2") (pintype "unspecified"))
      (node (ref "U1") (pin "B7") (pinfunction "SPKR_RP_B7") (pintype "input"))
    )
    (net (code "60") (name "/SPKR_R-") (class "Default")
      (node (ref "C3") (pin "1") (pinfunction "1_1") (pintype "input"))
      (node (ref "H5") (pin "1") (pinfunction "1_1") (pintype "unspecified"))
      (node (ref "U1") (pin "A7") (pinfunction "SPKR_RN_A7") (pintype "input"))
    )
    (net (code "61") (name "/UART_CTS") (class "Default")
      (node (ref "H11") (pin "4") (pinfunction "4_4") (pintype "unspecified"))
      (node (ref "U1") (pin "L3") (pinfunction "UART_CTS_L3") (pintype "input"))
    )
    (net (code "62") (name "/UART_RTS(P16)") (class "Default")
      (node (ref "H11") (pin "1") (pinfunction "1_1") (pintype "unspecified"))
    )
    (net (code "63") (name "/UART_RX") (class "Default")
      (node (ref "H11") (pin "3") (pinfunction "3_3") (pintype "unspecified"))
      (node (ref "U1") (pin "M2") (pinfunction "UART_RX_M2") (pintype "input"))
    )
    (net (code "64") (name "/UART_TX") (class "Default")
      (node (ref "H11") (pin "2") (pinfunction "2_2") (pintype "unspecified"))
      (node (ref "U1") (pin "M3") (pinfunction "UART_TX_M3") (pintype "input"))
    )
    (net (code "65") (name "/USB_DN") (class "Default")
      (node (ref "U1") (pin "M10") (pinfunction "USB_N_M10") (pintype "input"))
      (node (ref "USB1") (pin "5") (pinfunction "DN2_5") (pintype "unspecified"))
      (node (ref "USB1") (pin "7") (pinfunction "DN1_7") (pintype "unspecified"))
    )
    (net (code "66") (name "/USB_DP") (class "Default")
      (node (ref "U1") (pin "M9") (pinfunction "USB_P_M9") (pintype "input"))
      (node (ref "USB1") (pin "6") (pinfunction "DP1_6") (pintype "unspecified"))
      (node (ref "USB1") (pin "8") (pinfunction "DP2_8") (pintype "unspecified"))
    )
    (net (code "67") (name "/VBAT_SENSE") (class "Default")
      (node (ref "Q1") (pin "2") (pinfunction "C_2") (pintype "unspecified"))
      (node (ref "R3") (pin "2") (pinfunction "2_2") (pintype "unspecified"))
      (node (ref "U1") (pin "H11") (pinfunction "VBAT_SENSE_H11") (pintype "input"))
    )
    (net (code "68") (name "/VIN") (class "Default")
      (node (ref "D1") (pin "2") (pinfunction "2_2") (pintype "unspecified"))
      (node (ref "USB1") (pin "11") (pinfunction "VBUS_11") (pintype "unspecified"))
      (node (ref "USB1") (pin "2") (pinfunction "VBUS_2") (pintype "unspecified"))
    )
    (net (code "69") (name "/VREGENABLE") (class "Default")
      (node (ref "SW12") (pin "2") (pinfunction "2_2") (pintype "input"))
      (node (ref "U1") (pin "E10") (pinfunction "VREGENABLE_E10") (pintype "input"))
    )
    (net (code "70") (name "/XTAL_IN") (class "Default")
      (node (ref "U1") (pin "C1") (pinfunction "XTAL_IN_C1") (pintype "input"))
      (node (ref "X1") (pin "1") (pinfunction "OE#_1") (pintype "input"))
    )
    (net (code "71") (name "/XTAL_OUT") (class "Default")
      (node (ref "U1") (pin "B1") (pinfunction "XTAL_OUT_B1") (pintype "input"))
      (node (ref "X1") (pin "3") (pinfunction "OUT_3") (pintype "input"))
    )
    (net (code "72") (name "6V5") (class "Default")
      (node (ref "C29") (pin "1") (pinfunction "1_1") (pintype "input"))
      (node (ref "C30") (pin "2") (pinfunction "2_2") (pintype "input"))
      (node (ref "C32") (pin "1") (pinfunction "1_1") (pintype "input"))
      (node (ref "C35") (pin "1") (pinfunction "1_1") (pintype "unspecified"))
      (node (ref "D4") (pin "1") (pinfunction "C_1") (pintype "unspecified"))
      (node (ref "LED6") (pin "2") (pinfunction "A_2") (pintype "input"))
      (node (ref "NC1") (pin "1") (pinfunction "1_1") (pintype "input"))
      (node (ref "R17") (pin "2") (pinfunction "2_2") (pintype "input"))
      (node (ref "SW12") (pin "6") (pinfunction "6_6") (pintype "input"))
      (node (ref "U4") (pin "6") (pinfunction "VDD_6") (pintype "unspecified"))
    )
    (net (code "73") (name "AGND") (class "Default")
      (node (ref "C13") (pin "2") (pinfunction "2_2") (pintype "input"))
      (node (ref "C17") (pin "1") (pinfunction "1_1") (pintype "input"))
      (node (ref "C20") (pin "1") (pinfunction "1_1") (pintype "input"))
      (node (ref "C21") (pin "2") (pinfunction "2_2") (pintype "input"))
      (node (ref "C32") (pin "2") (pinfunction "2_2") (pintype "input"))
      (node (ref "C33") (pin "2") (pinfunction "2_2") (pintype "input"))
      (node (ref "C35") (pin "2") (pinfunction "2_2") (pintype "unspecified"))
      (node (ref "MIC1") (pin "2") (pinfunction "2_2") (pintype "input"))
      (node (ref "MIC2") (pin "2") (pinfunction "2_2") (pintype "input"))
      (node (ref "NC1") (pin "2") (pinfunction "2_2") (pintype "input"))
      (node (ref "R11") (pin "2") (pinfunction "2_2") (pintype "unspecified"))
      (node (ref "R26") (pin "1") (pinfunction "1_1") (pintype "input"))
      (node (ref "U1") (pin "B6") (pinfunction "VSS_AUDIO_DRV_B6") (pintype "input"))
      (node (ref "U1") (pin "C9") (pinfunction "VSS_AUDIO_C9") (pintype "input"))
      (node (ref "U4") (pin "7") (pinfunction "GND_7") (pintype "unspecified"))
    )
    (net (code "74") (name "GND") (class "Default")
      (node (ref "C10") (pin "2") (pinfunction "2_2") (pintype "input"))
      (node (ref "C11") (pin "2") (pinfunction "2_2") (pintype "input"))
      (node (ref "C14") (pin "2") (pinfunction "2_2") (pintype "input"))
      (node (ref "C24") (pin "2") (pinfunction "2_2") (pintype "input"))
      (node (ref "C25") (pin "2") (pinfunction "2_2") (pintype "unspecified"))
      (node (ref "C26") (pin "2") (pinfunction "2_2") (pintype "unspecified"))
      (node (ref "C27") (pin "1") (pinfunction "1_1") (pintype "input"))
      (node (ref "C4") (pin "1") (pinfunction "1_1") (pintype "input"))
      (node (ref "C5") (pin "2") (pinfunction "2_2") (pintype "input"))
      (node (ref "C6") (pin "1") (pinfunction "1_1") (pintype "unspecified"))
      (node (ref "C7") (pin "1") (pinfunction "1_1") (pintype "input"))
      (node (ref "C8") (pin "1") (pinfunction "1_1") (pintype "input"))
      (node (ref "C9") (pin "1") (pinfunction "1_1") (pintype "input"))
      (node (ref "H13") (pin "2") (pinfunction "2_2") (pintype "input"))
      (node (ref "H9") (pin "1") (pinfunction "1_1") (pintype "input"))
      (node (ref "H9") (pin "2") (pinfunction "2_2") (pintype "input"))
      (node (ref "H9") (pin "3") (pinfunction "3_3") (pintype "input"))
      (node (ref "H9") (pin "4") (pinfunction "4_4") (pintype "input"))
      (node (ref "H9") (pin "5") (pinfunction "5_5") (pintype "input"))
      (node (ref "R1") (pin "2") (pinfunction "2_2") (pintype "input"))
      (node (ref "R11") (pin "1") (pinfunction "1_1") (pintype "unspecified"))
      (node (ref "R2") (pin "2") (pinfunction "2_2") (pintype "input"))
      (node (ref "R22") (pin "1") (pinfunction "1_1") (pintype "unspecified"))
      (node (ref "R23") (pin "1") (pinfunction "1_1") (pintype "input"))
      (node (ref "R24") (pin "1") (pinfunction "1_1") (pintype "input"))
      (node (ref "R25") (pin "1") (pinfunction "1_1") (pintype "input"))
      (node (ref "SW1") (pin "2") (pinfunction "2_2") (pintype "unspecified"))
      (node (ref "SW2") (pin "2") (pinfunction "2_2") (pintype "unspecified"))
      (node (ref "SW3") (pin "2") (pinfunction "2_2") (pintype "unspecified"))
      (node (ref "SW4") (pin "2") (pinfunction "2_2") (pintype "unspecified"))
      (node (ref "SW5") (pin "2") (pinfunction "2_2") (pintype "unspecified"))
      (node (ref "SW6") (pin "2") (pinfunction "2_2") (pintype "unspecified"))
      (node (ref "SW7") (pin "2") (pinfunction "2_2") (pintype "unspecified"))
      (node (ref "U1") (pin "A4") (pinfunction "VSS_BT_RF_A4") (pintype "input"))
      (node (ref "U1") (pin "B2") (pinfunction "VSS_BT_LO_AUX_B2") (pintype "input"))
      (node (ref "U1") (pin "B3") (pinfunction "NC/GND_B3") (pintype "input"))
      (node (ref "U1") (pin "B4") (pinfunction "NC/GND_B4") (pintype "input"))
      (node (ref "U1") (pin "B5") (pinfunction "VSS_BT_RF_B5") (pintype "input"))
      (node (ref "U1") (pin "D10") (pinfunction "VSS_DIG_D10") (pintype "input"))
      (node (ref "U1") (pin "F7") (pinfunction "VSS_DIG_F7") (pintype "input"))
      (node (ref "U1") (pin "G10") (pinfunction "VSS_DIG_G10") (pintype "input"))
      (node (ref "U1") (pin "G7") (pinfunction "VSS_DIG_G7") (pintype "input"))
      (node (ref "U1") (pin "H10") (pinfunction "VSS_DIG_H10") (pintype "input"))
      (node (ref "U1") (pin "J11") (pinfunction "VSS_SMPS_1V8_J11") (pintype "input"))
      (node (ref "U1") (pin "M12") (pinfunction "VSS_SMPS_1V35_M12") (pintype "input"))
      (node (ref "USB1") (pin "1") (pinfunction "GND_1") (pintype "unspecified"))
      (node (ref "USB1") (pin "12") (pinfunction "GND_12") (pintype "unspecified"))
      (node (ref "USB1") (pin "13") (pinfunction "SHELL_13") (pintype "unspecified"))
      (node (ref "USB1") (pin "14") (pinfunction "SHELL_14") (pintype "unspecified"))
      (node (ref "X1") (pin "2") (pinfunction "GND_2") (pintype "input"))
      (node (ref "X1") (pin "4") (pinfunction "VDD_4") (pintype "input"))
    )
    (net (code "75") (name "Net-(C3-Pad2)") (class "Default")
      (node (ref "C3") (pin "2") (pinfunction "2_2") (pintype "input"))
      (node (ref "R19") (pin "1") (pinfunction "1_1") (pintype "input"))
    )
    (net (code "76") (name "Net-(C14-Pad1)") (class "Default")
      (node (ref "C14") (pin "1") (pinfunction "1_1") (pintype "input"))
      (node (ref "U1") (pin "E12") (pinfunction "VDD_DIG_EFLASH_E12") (pintype "input"))
      (node (ref "U1") (pin "K2") (pinfunction "VDD_DIG_EFLASH_K2") (pintype "input"))
    )
    (net (code "77") (name "Net-(C16-Pad1)") (class "Default")
      (node (ref "C16") (pin "1") (pinfunction "1_1") (pintype "input"))
      (node (ref "C17") (pin "2") (pinfunction "2_2") (pintype "input"))
      (node (ref "L10") (pin "2") (pinfunction "2_2") (pintype "unspecified"))
      (node (ref "R9") (pin "2") (pinfunction "2_2") (pintype "unspecified"))
    )
    (net (code "78") (name "Net-(C19-Pad1)") (class "Default")
      (node (ref "C19") (pin "1") (pinfunction "1_1") (pintype "input"))
      (node (ref "C20") (pin "2") (pinfunction "2_2") (pintype "input"))
      (node (ref "L11") (pin "2") (pinfunction "2_2") (pintype "unspecified"))
      (node (ref "R10") (pin "2") (pinfunction "2_2") (pintype "unspecified"))
    )
    (net (code "79") (name "Net-(C23-Pad1)") (class "Default")
      (node (ref "C23") (pin "1") (pinfunction "1_1") (pintype "unspecified"))
      (node (ref "U1") (pin "G11") (pinfunction "VCHG_G11") (pintype "input"))
      (node (ref "U1") (pin "G12") (pinfunction "VCHG_G12") (pintype "input"))
    )
    (net (code "80") (name "Net-(C24-Pad1)") (class "Default")
      (node (ref "C24") (pin "1") (pinfunction "1_1") (pintype "input"))
      (node (ref "R16") (pin "2") (pinfunction "2_2") (pintype "input"))
    )
    (net (code "81") (name "Net-(C31-Pad2)") (class "Default")
      (node (ref "C31") (pin "2") (pinfunction "2_2") (pintype "input"))
      (node (ref "R4") (pin "1") (pinfunction "1_1") (pintype "input"))
    )
    (net (code "82") (name "Net-(D1-Pad1)") (class "Default")
      (node (ref "D1") (pin "1") (pinfunction "1_1") (pintype "unspecified"))
      (node (ref "F2") (pin "2") (pinfunction "2_2") (pintype "unspecified"))
    )
    (net (code "83") (name "Net-(D2-A)") (class "Default")
      (node (ref "D2") (pin "1") (pinfunction "A_1") (pintype "unspecified"))
      (node (ref "D3") (pin "1") (pinfunction "A_1") (pintype "unspecified"))
      (node (ref "LED1") (pin "2") (pinfunction "A_2") (pintype "input"))
      (node (ref "LED2") (pin "2") (pinfunction "A_2") (pintype "input"))
      (node (ref "LED3") (pin "2") (pinfunction "A_2") (pintype "input"))
    )
    (net (code "84") (name "Net-(D4-A)") (class "Default")
      (node (ref "D4") (pin "2") (pinfunction "A_2") (pintype "unspecified"))
      (node (ref "L7") (pin "1") (pinfunction "1_1") (pintype "unspecified"))
      (node (ref "U2") (pin "1") (pinfunction "SW_1") (pintype "input"))
    )
    (net (code "85") (name "Net-(F1-Pad2)") (class "Default")
      (node (ref "F1") (pin "2") (pinfunction "2_2") (pintype "unspecified"))
      (node (ref "H13") (pin "1") (pinfunction "1_1") (pintype "input"))
    )
    (net (code "86") (name "Net-(L10-Pad1)") (class "Default")
      (node (ref "L10") (pin "1") (pinfunction "1_1") (pintype "unspecified"))
      (node (ref "MIC1") (pin "1") (pinfunction "1_1") (pintype "input"))
    )
    (net (code "87") (name "Net-(L11-Pad1)") (class "Default")
      (node (ref "L11") (pin "1") (pinfunction "1_1") (pintype "unspecified"))
      (node (ref "MIC2") (pin "1") (pinfunction "1_1") (pintype "input"))
    )
    (net (code "88") (name "Net-(LED1-K)") (class "Default")
      (node (ref "LED1") (pin "1") (pinfunction "K_1") (pintype "input"))
      (node (ref "R13") (pin "2") (pinfunction "2_2") (pintype "input"))
    )
    (net (code "89") (name "Net-(LED2-K)") (class "Default")
      (node (ref "LED2") (pin "1") (pinfunction "K_1") (pintype "input"))
      (node (ref "R14") (pin "2") (pinfunction "2_2") (pintype "input"))
    )
    (net (code "90") (name "Net-(LED3-K)") (class "Default")
      (node (ref "LED3") (pin "1") (pinfunction "K_1") (pintype "input"))
      (node (ref "R15") (pin "2") (pinfunction "2_2") (pintype "input"))
    )
    (net (code "91") (name "Net-(LED4-K)") (class "Default")
      (node (ref "LED4") (pin "1") (pinfunction "K_1") (pintype "input"))
      (node (ref "R23") (pin "2") (pinfunction "2_2") (pintype "input"))
    )
    (net (code "92") (name "Net-(LED5-K)") (class "Default")
      (node (ref "LED5") (pin "1") (pinfunction "K_1") (pintype "input"))
      (node (ref "R24") (pin "2") (pinfunction "2_2") (pintype "input"))
    )
    (net (code "93") (name "Net-(LED6-K)") (class "Default")
      (node (ref "LED6") (pin "1") (pinfunction "K_1") (pintype "input"))
      (node (ref "R25") (pin "2") (pinfunction "2_2") (pintype "input"))
    )
    (net (code "94") (name "Net-(R26-Pad2)") (class "Default")
      (node (ref "R26") (pin "2") (pinfunction "2_2") (pintype "input"))
      (node (ref "SW12") (pin "5") (pinfunction "5_5") (pintype "input"))
    )
    (net (code "95") (name "Net-(U1-AU_REF)") (class "Default")
      (node (ref "C21") (pin "1") (pinfunction "1_1") (pintype "input"))
      (node (ref "U1") (pin "B9") (pinfunction "AU_REF_B9") (pintype "input"))
    )
    (net (code "96") (name "Net-(U1-LX_1V8)") (class "Default")
      (node (ref "L8") (pin "1") (pinfunction "1_1") (pintype "input"))
      (node (ref "U1") (pin "J12") (pinfunction "LX_1V8_J12") (pintype "input"))
    )
    (net (code "97") (name "Net-(U1-LX_1V35)") (class "Default")
      (node (ref "L9") (pin "1") (pinfunction "1_1") (pintype "input"))
      (node (ref "U1") (pin "L12") (pinfunction "LX_1V35_L12") (pintype "input"))
    )
    (net (code "98") (name "Net-(U1-VDD_AUX)") (class "Default")
      (node (ref "C8") (pin "2") (pinfunction "2_2") (pintype "input"))
      (node (ref "R7") (pin "1") (pinfunction "1_1") (pintype "input"))
      (node (ref "U1") (pin "C3") (pinfunction "VDD_AUX_C3") (pintype "input"))
    )
    (net (code "99") (name "Net-(U1-VDD_BT_LO)") (class "Default")
      (node (ref "C10") (pin "1") (pinfunction "1_1") (pintype "input"))
      (node (ref "R8") (pin "1") (pinfunction "1_1") (pintype "unspecified"))
      (node (ref "U1") (pin "A2") (pinfunction "VDD_BT_LO_A2") (pintype "input"))
    )
    (net (code "100") (name "Net-(U2-FB)") (class "Default")
      (node (ref "R17") (pin "1") (pinfunction "1_1") (pintype "input"))
      (node (ref "R18") (pin "2") (pinfunction "2_2") (pintype "input"))
      (node (ref "U2") (pin "3") (pinfunction "FB_3") (pintype "input"))
    )
    (net (code "101") (name "Net-(U4-BYPASS)") (class "Default")
      (node (ref "C33") (pin "1") (pinfunction "1_1") (pintype "input"))
      (node (ref "U4") (pin "2") (pinfunction "BYPASS_2") (pintype "unspecified"))
    )
    (net (code "102") (name "Net-(U4-IN+)") (class "Default")
      (node (ref "R4") (pin "2") (pinfunction "2_2") (pintype "input"))
      (node (ref "U4") (pin "4") (pinfunction "IN+_4") (pintype "unspecified"))
    )
    (net (code "103") (name "Net-(U4-IN-)") (class "Default")
      (node (ref "R19") (pin "2") (pinfunction "2_2") (pintype "input"))
      (node (ref "U4") (pin "3") (pinfunction "IN-_3") (pintype "unspecified"))
    )
    (net (code "104") (name "Net-(USB1-CC1)") (class "Default")
      (node (ref "R2") (pin "1") (pinfunction "1_1") (pintype "input"))
      (node (ref "USB1") (pin "4") (pinfunction "CC1_4") (pintype "unspecified"))
    )
    (net (code "105") (name "Net-(USB1-CC2)") (class "Default")
      (node (ref "R1") (pin "1") (pinfunction "1_1") (pintype "input"))
      (node (ref "USB1") (pin "10") (pinfunction "CC2_10") (pintype "unspecified"))
    )
    (net (code "106") (name "PGND") (class "Default")
      (node (ref "C29") (pin "2") (pinfunction "2_2") (pintype "input"))
      (node (ref "C30") (pin "1") (pinfunction "1_1") (pintype "input"))
      (node (ref "R18") (pin "1") (pinfunction "1_1") (pintype "input"))
      (node (ref "R22") (pin "2") (pinfunction "2_2") (pintype "unspecified"))
      (node (ref "U2") (pin "2") (pinfunction "GND_2") (pintype "input"))
    )
    (net (code "107") (name "VBAT+") (class "Default")
      (node (ref "C4") (pin "2") (pinfunction "2_2") (pintype "input"))
      (node (ref "D3") (pin "2") (pinfunction "K_2") (pintype "unspecified"))
      (node (ref "D5") (pin "2") (pinfunction "A_2") (pintype "unspecified"))
      (node (ref "F1") (pin "1") (pinfunction "1_1") (pintype "unspecified"))
      (node (ref "H6") (pin "4") (pinfunction "4_4") (pintype "input"))
      (node (ref "H8") (pin "1") (pinfunction "1_1") (pintype "input"))
      (node (ref "H8") (pin "2") (pinfunction "2_2") (pintype "input"))
      (node (ref "LED5") (pin "2") (pinfunction "A_2") (pintype "input"))
      (node (ref "R16") (pin "1") (pinfunction "1_1") (pintype "input"))
      (node (ref "R3") (pin "1") (pinfunction "1_1") (pintype "unspecified"))
      (node (ref "SW12") (pin "7") (pinfunction "7_7") (pintype "input"))
      (node (ref "U1") (pin "H12") (pinfunction "VBAT_H12") (pintype "input"))
      (node (ref "U1") (pin "K12") (pinfunction "SMP_VBAT_K12") (pintype "input"))
    )
    (net (code "108") (name "VBUS") (class "Default")
      (node (ref "C23") (pin "2") (pinfunction "2_2") (pintype "unspecified"))
      (node (ref "D2") (pin "2") (pinfunction "K_2") (pintype "unspecified"))
      (node (ref "D6") (pin "2") (pinfunction "A_2") (pintype "unspecified"))
      (node (ref "F2") (pin "1") (pinfunction "1_1") (pintype "unspecified"))
      (node (ref "H6") (pin "5") (pinfunction "5_5") (pintype "input"))
      (node (ref "H8") (pin "3") (pinfunction "3_3") (pintype "input"))
      (node (ref "H8") (pin "4") (pinfunction "4_4") (pintype "input"))
      (node (ref "LED4") (pin "2") (pinfunction "A_2") (pintype "input"))
      (node (ref "Q1") (pin "3") (pinfunction "E_3") (pintype "unspecified"))
    )
    (net (code "109") (name "unconnected-(AE1-Pad2)") (class "Default")
      (node (ref "AE1") (pin "2") (pinfunction "2_2") (pintype "input"))
    )
    (net (code "110") (name "unconnected-(U1-NC-PadF6)") (class "Default")
      (node (ref "U1") (pin "F6") (pinfunction "NC_F6") (pintype "input+no_connect"))
    )
    (net (code "111") (name "unconnected-(U1-NC-PadG1)") (class "Default")
      (node (ref "U1") (pin "G1") (pinfunction "NC_G1") (pintype "input+no_connect"))
    )
    (net (code "112") (name "unconnected-(U1-NC-PadG6)") (class "Default")
      (node (ref "U1") (pin "G6") (pinfunction "NC_G6") (pintype "input+no_connect"))
    )
    (net (code "113") (name "unconnected-(U1-NC-PadH1)") (class "Default")
      (node (ref "U1") (pin "H1") (pinfunction "NC_H1") (pintype "input+no_connect"))
    )
    (net (code "114") (name "unconnected-(U1-NC-PadJ2)") (class "Default")
      (node (ref "U1") (pin "J2") (pinfunction "NC_J2") (pintype "input+no_connect"))
    )
    (net (code "115") (name "unconnected-(U1-NC-PadJ3)") (class "Default")
      (node (ref "U1") (pin "J3") (pinfunction "NC_J3") (pintype "input+no_connect"))
    )
    (net (code "116") (name "unconnected-(U1-PIO[18]-PadH3)") (class "Default")
      (node (ref "U1") (pin "H3") (pinfunction "PIO[18]_H3") (pintype "input"))
    )
    (net (code "117") (name "unconnected-(U1-PIO[19]-PadH2)") (class "Default")
      (node (ref "U1") (pin "H2") (pinfunction "PIO[19]_H2") (pintype "input+no_connect"))
    )
    (net (code "118") (name "unconnected-(U1-PIO[20]-PadG2)") (class "Default")
      (node (ref "U1") (pin "G2") (pinfunction "PIO[20]_G2") (pintype "input+no_connect"))
    )
    (net (code "119") (name "unconnected-(U1-PIO[21]-PadC12)") (class "Default")
      (node (ref "U1") (pin "C12") (pinfunction "PIO[21]_C12") (pintype "input+no_connect"))
    )
    (net (code "120") (name "unconnected-(U1-PIO[22].-PadB12)") (class "Default")
      (node (ref "U1") (pin "B12") (pinfunction "PIO[22]._B12") (pintype "input+no_connect"))
    )
    (net (code "121") (name "unconnected-(U1-PIO[23]-PadD11)") (class "Default")
      (node (ref "U1") (pin "D11") (pinfunction "PIO[23]_D11") (pintype "input+no_connect"))
    )
    (net (code "122") (name "unconnected-(U1-PIO[24]-PadB10)") (class "Default")
      (node (ref "U1") (pin "B10") (pinfunction "PIO[24]_B10") (pintype "input+no_connect"))
    )
    (net (code "123") (name "unconnected-(U1-PIO[25]-PadC11)") (class "Default")
      (node (ref "U1") (pin "C11") (pinfunction "PIO[25]_C11") (pintype "input+no_connect"))
    )
    (net (code "124") (name "unconnected-(U1-PIO[26]-PadB11)") (class "Default")
      (node (ref "U1") (pin "B11") (pinfunction "PIO[26]_B11") (pintype "input+no_connect"))
    )
    (net (code "125") (name "unconnected-(U1-PIO[27]-PadC10)") (class "Default")
      (node (ref "U1") (pin "C10") (pinfunction "PIO[27]_C10") (pintype "input+no_connect"))
    )
    (net (code "126") (name "unconnected-(U1-PIO[28]-PadD12)") (class "Default")
      (node (ref "U1") (pin "D12") (pinfunction "PIO[28]_D12") (pintype "input+no_connect"))
    )
    (net (code "127") (name "unconnected-(U1-VDD_ANA-PadC2)") (class "Default")
      (node (ref "U1") (pin "C2") (pinfunction "VDD_ANA_C2") (pintype "input+no_connect"))
    )
    (net (code "128") (name "unconnected-(U2-NC-Pad6)") (class "Default")
      (node (ref "U2") (pin "6") (pinfunction "NC_6") (pintype "input+no_connect"))
    )
    (net (code "129") (name "unconnected-(USB1-SBU1-Pad9)") (class "Default")
      (node (ref "USB1") (pin "9") (pinfunction "SBU1_9") (pintype "unspecified+no_connect"))
    )
    (net (code "130") (name "unconnected-(USB1-SBU2-Pad3)") (class "Default")
      (node (ref "USB1") (pin "3") (pinfunction "SBU2_3") (pintype "unspecified+no_connect"))
    )
  )
)
